# Sildr_1_0b.net
KiCad netlist of a schematic drawn in EAGLE
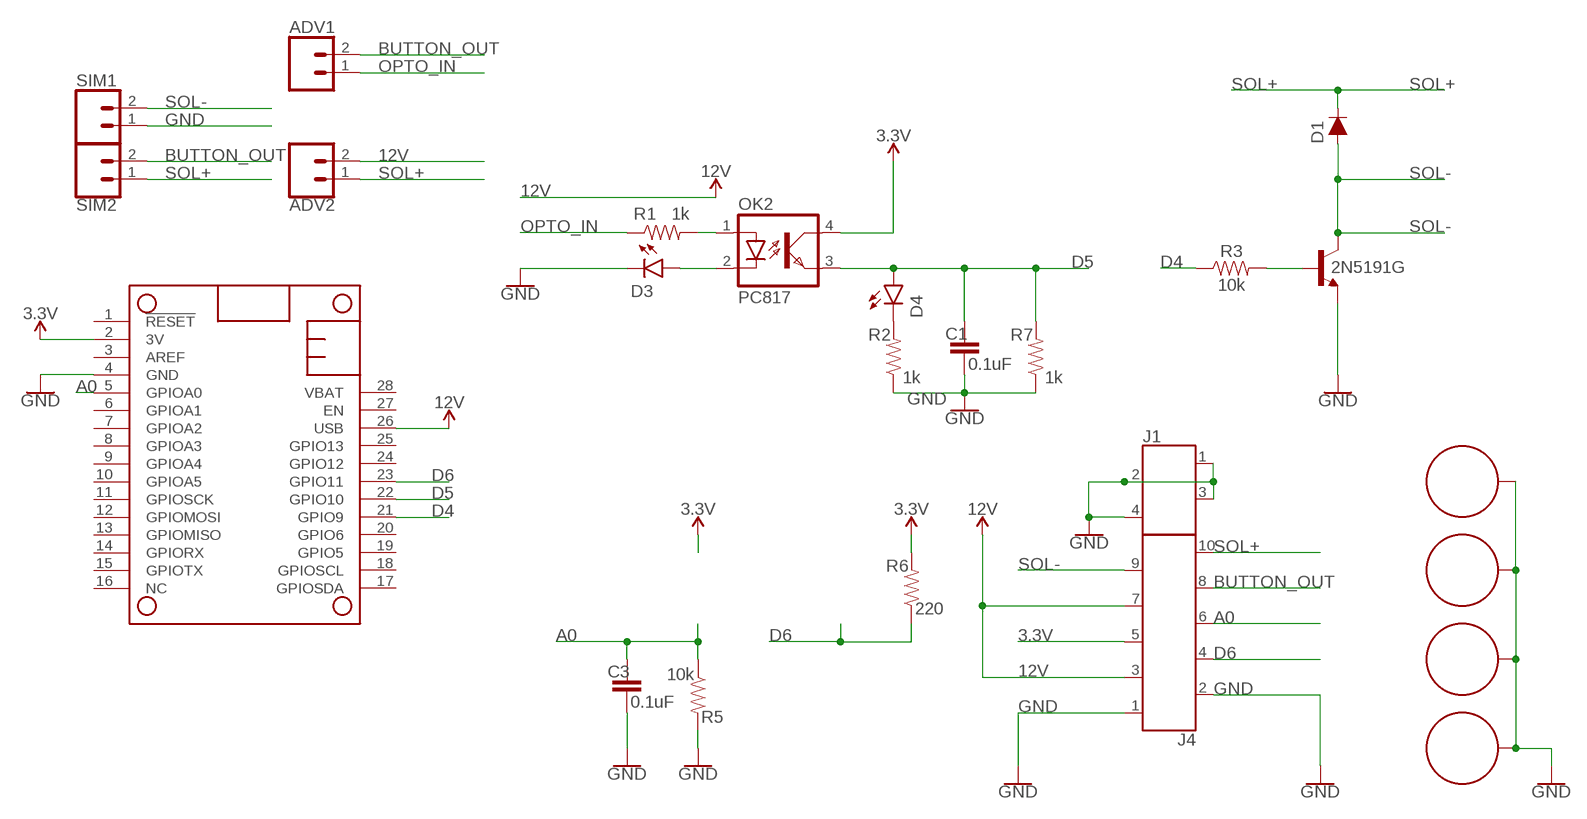
[diagram p0: schematic, sheet 1]

(export (version "E")
  (design (tool "Eeschema 10.0.6"))
  (components
    (comp (ref "2N5191G")
      (value "2SC1944")
      (footprint "eagle-import:T-30_V")
      (libsource (lib "eagle-import") (part "2SC1944"))
    )
    (comp (ref "ADV1")
      (value "CONN_02")
      (footprint "eagle-import:1X02")
      (libsource (lib "eagle-import") (part "CONN_02"))
    )
    (comp (ref "ADV2")
      (value "CONN_02")
      (footprint "eagle-import:1X02")
      (libsource (lib "eagle-import") (part "CONN_02"))
    )
    (comp (ref "C1")
      (value "0.1uF")
      (footprint "eagle-import:CAP-PTH-SMALL-KIT")
      (libsource (lib "eagle-import") (part "0.1UF-KIT-EZ-50V-20%"))
    )
    (comp (ref "C3")
      (value "0.1uF")
      (footprint "eagle-import:CAP-PTH-SMALL-KIT")
      (libsource (lib "eagle-import") (part "0.1UF-KIT-EZ-50V-20%"))
    )
    (comp (ref "D1")
      (value "1A/50V/1.1V")
      (footprint "eagle-import:DIODE-1N4001")
      (libsource (lib "eagle-import") (part "DIODE-PTH"))
    )
    (comp (ref "D3")
      (value "LED3MM")
      (footprint "eagle-import:LED_3MM")
      (libsource (lib "eagle-import") (part "LED3MM"))
    )
    (comp (ref "D4")
      (value "LED3MM")
      (footprint "eagle-import:LED_3MM")
      (libsource (lib "eagle-import") (part "LED3MM"))
    )
    (comp (ref "H1")
      (value "STANDOFF_ELECTRICAL")
      (footprint "eagle-import:STANDOFF-ELECTRICAL")
      (libsource (lib "eagle-import") (part "STANDOFF_ELECTRICAL"))
    )
    (comp (ref "H2")
      (value "STANDOFF_ELECTRICAL")
      (footprint "eagle-import:STANDOFF-ELECTRICAL")
      (libsource (lib "eagle-import") (part "STANDOFF_ELECTRICAL"))
    )
    (comp (ref "H3")
      (value "STANDOFF_ELECTRICAL")
      (footprint "eagle-import:STANDOFF-ELECTRICAL")
      (libsource (lib "eagle-import") (part "STANDOFF_ELECTRICAL"))
    )
    (comp (ref "H6")
      (value "STANDOFF_ELECTRICAL")
      (footprint "eagle-import:STANDOFF-ELECTRICAL")
      (libsource (lib "eagle-import") (part "STANDOFF_ELECTRICAL"))
    )
    (comp (ref "J1")
      (value "691412320004")
      (footprint "eagle-import:691412320004")
      (libsource (lib "eagle-import") (part "691412320004"))
    )
    (comp (ref "J4")
      (value "691412320010")
      (footprint "eagle-import:691412320010")
      (libsource (lib "eagle-import") (part "691412320010"))
    )
    (comp (ref "MS1")
      (value "FEATHERWING_NODIM")
      (footprint "eagle-import:FEATHERWING_DIM")
      (libsource (lib "eagle-import") (part "FEATHERWING_NODIM"))
    )
    (comp (ref "OK2")
      (value "PC817")
      (footprint "eagle-import:DIL04")
      (fields (field (name "MPN") "PC817X4J000F"))
      (libsource (lib "eagle-import") (part "PC817"))
    )
    (comp (ref "R1")
      (value "1k")
      (footprint "eagle-import:AXIAL-0.3")
      (libsource (lib "eagle-import") (part "10KOHM-HORIZ-1/4W-5%"))
    )
    (comp (ref "R2")
      (value "1k")
      (footprint "eagle-import:AXIAL-0.3")
      (libsource (lib "eagle-import") (part "10KOHM-HORIZ-1/4W-5%"))
    )
    (comp (ref "R3")
      (value "10k")
      (footprint "eagle-import:AXIAL-0.3")
      (libsource (lib "eagle-import") (part "10KOHM-HORIZ-1/4W-5%"))
    )
    (comp (ref "R5")
      (value "10k")
      (footprint "eagle-import:AXIAL-0.3")
      (libsource (lib "eagle-import") (part "10KOHM-HORIZ-1/4W-5%"))
    )
    (comp (ref "R6")
      (value "220")
      (footprint "eagle-import:AXIAL-0.3")
      (libsource (lib "eagle-import") (part "10KOHM-HORIZ-1/4W-5%"))
    )
    (comp (ref "R7")
      (value "1k")
      (footprint "eagle-import:AXIAL-0.3")
      (libsource (lib "eagle-import") (part "10KOHM-HORIZ-1/4W-5%"))
    )
    (comp (ref "SIM1")
      (value "CONN_02")
      (footprint "eagle-import:1X02")
      (libsource (lib "eagle-import") (part "CONN_02"))
    )
    (comp (ref "SIM2")
      (value "CONN_02")
      (footprint "eagle-import:1X02")
      (libsource (lib "eagle-import") (part "CONN_02"))
    )
  )
  (nets
    (net (code "1") (name "/A0") (class "Default")
      (node (ref "C3") (pin "1") (pinfunction "1_1") (pintype "passive"))
      (node (ref "J4") (pin "6") (pinfunction "6_6") (pintype "passive"))
      (node (ref "MS1") (pin "5") (pinfunction "GPIOA0_5") (pintype "bidirectional"))
      (node (ref "R5") (pin "P$1") (pinfunction "1_P$1") (pintype "passive"))
    )
    (net (code "2") (name "/BUTTON_OUT") (class "Default")
      (node (ref "ADV1") (pin "2") (pinfunction "2_2") (pintype "passive"))
      (node (ref "J4") (pin "8") (pinfunction "8_8") (pintype "passive"))
      (node (ref "SIM2") (pin "2") (pinfunction "2_2") (pintype "passive"))
    )
    (net (code "3") (name "/D4") (class "Default")
      (node (ref "MS1") (pin "21") (pinfunction "GPIO9_21") (pintype "bidirectional"))
      (node (ref "R3") (pin "P$1") (pinfunction "1_P$1") (pintype "passive"))
    )
    (net (code "4") (name "/D5") (class "Default")
      (node (ref "C1") (pin "1") (pinfunction "1_1") (pintype "passive"))
      (node (ref "D4") (pin "A") (pinfunction "A_A") (pintype "passive"))
      (node (ref "MS1") (pin "22") (pinfunction "GPIO10_22") (pintype "bidirectional"))
      (node (ref "OK2") (pin "3") (pinfunction "EMIT_3") (pintype "passive"))
      (node (ref "R7") (pin "P$2") (pinfunction "2_P$2") (pintype "passive"))
    )
    (net (code "5") (name "/D6") (class "Default")
      (node (ref "J4") (pin "4") (pinfunction "4_4") (pintype "passive"))
      (node (ref "MS1") (pin "23") (pinfunction "GPIO11_23") (pintype "bidirectional"))
      (node (ref "R6") (pin "P$1") (pinfunction "1_P$1") (pintype "passive"))
    )
    (net (code "6") (name "/OPTO_IN") (class "Default")
      (node (ref "ADV1") (pin "1") (pinfunction "1_1") (pintype "passive"))
      (node (ref "R1") (pin "P$1") (pinfunction "1_P$1") (pintype "passive"))
    )
    (net (code "7") (name "/SOL+") (class "Default")
      (node (ref "ADV2") (pin "1") (pinfunction "1_1") (pintype "passive"))
      (node (ref "D1") (pin "C") (pinfunction "C_C") (pintype "passive"))
      (node (ref "J4") (pin "10") (pinfunction "10_10") (pintype "passive"))
      (node (ref "SIM2") (pin "1") (pinfunction "1_1") (pintype "passive"))
    )
    (net (code "8") (name "/SOL-") (class "Default")
      (node (ref "2N5191G") (pin "2") (pinfunction "C_2") (pintype "passive"))
      (node (ref "D1") (pin "A") (pinfunction "A_A") (pintype "passive"))
      (node (ref "J4") (pin "9") (pinfunction "9_9") (pintype "passive"))
      (node (ref "SIM1") (pin "2") (pinfunction "2_2") (pintype "passive"))
    )
    (net (code "9") (name "/VBAT") (class "Default")
      (node (ref "MS1") (pin "28") (pinfunction "VBAT_28") (pintype "power_in"))
    )
    (net (code "10") (name "3.3V") (class "Default")
      (node (ref "J4") (pin "5") (pinfunction "5_5") (pintype "passive"))
      (node (ref "MS1") (pin "2") (pinfunction "3V_2") (pintype "power_in"))
      (node (ref "OK2") (pin "4") (pinfunction "COL_4") (pintype "passive"))
      (node (ref "R6") (pin "P$2") (pinfunction "2_P$2") (pintype "passive"))
    )
    (net (code "11") (name "12V") (class "Default")
      (node (ref "ADV2") (pin "2") (pinfunction "2_2") (pintype "passive"))
      (node (ref "J4") (pin "3") (pinfunction "3_3") (pintype "passive"))
      (node (ref "J4") (pin "7") (pinfunction "7_7") (pintype "passive"))
      (node (ref "MS1") (pin "26") (pinfunction "USB_26") (pintype "power_in"))
    )
    (net (code "12") (name "GND") (class "Default")
      (node (ref "2N5191G") (pin "3") (pinfunction "E_3") (pintype "passive"))
      (node (ref "C1") (pin "2") (pinfunction "2_2") (pintype "passive"))
      (node (ref "C3") (pin "2") (pinfunction "2_2") (pintype "passive"))
      (node (ref "D3") (pin "K") (pinfunction "C_K") (pintype "passive"))
      (node (ref "H1") (pin "P1") (pinfunction "P$1_P1") (pintype "bidirectional"))
      (node (ref "H2") (pin "P1") (pinfunction "P$1_P1") (pintype "bidirectional"))
      (node (ref "H3") (pin "P1") (pinfunction "P$1_P1") (pintype "bidirectional"))
      (node (ref "H6") (pin "P1") (pinfunction "P$1_P1") (pintype "bidirectional"))
      (node (ref "J1") (pin "1") (pinfunction "1_1") (pintype "passive"))
      (node (ref "J1") (pin "2") (pinfunction "2_2") (pintype "passive"))
      (node (ref "J1") (pin "3") (pinfunction "3_3") (pintype "passive"))
      (node (ref "J1") (pin "4") (pinfunction "4_4") (pintype "passive"))
      (node (ref "J4") (pin "1") (pinfunction "1_1") (pintype "passive"))
      (node (ref "J4") (pin "2") (pinfunction "2_2") (pintype "passive"))
      (node (ref "MS1") (pin "4") (pinfunction "GND_4") (pintype "power_in"))
      (node (ref "R2") (pin "P$1") (pinfunction "1_P$1") (pintype "passive"))
      (node (ref "R5") (pin "P$2") (pinfunction "2_P$2") (pintype "passive"))
      (node (ref "R7") (pin "P$1") (pinfunction "1_P$1") (pintype "passive"))
      (node (ref "SIM1") (pin "1") (pinfunction "1_1") (pintype "passive"))
    )
    (net (code "13") (name "Net-(2N5191G-B)") (class "Default")
      (node (ref "2N5191G") (pin "1") (pinfunction "B_1") (pintype "passive"))
      (node (ref "R3") (pin "P$2") (pinfunction "2_P$2") (pintype "passive"))
    )
    (net (code "14") (name "Net-(D4-C)") (class "Default")
      (node (ref "D4") (pin "K") (pinfunction "C_K") (pintype "passive"))
      (node (ref "R2") (pin "P$2") (pinfunction "2_P$2") (pintype "passive"))
    )
    (net (code "15") (name "Net-(OK2-A)") (class "Default")
      (node (ref "OK2") (pin "1") (pinfunction "A_1") (pintype "passive"))
      (node (ref "R1") (pin "P$2") (pinfunction "2_P$2") (pintype "passive"))
    )
    (net (code "16") (name "Net-(OK2-C)") (class "Default")
      (node (ref "D3") (pin "A") (pinfunction "A_A") (pintype "passive"))
      (node (ref "OK2") (pin "2") (pinfunction "C_2") (pintype "passive"))
    )
    (net (code "17") (name "unconnected-(MS1-AREF-Pad3)") (class "Default")
      (node (ref "MS1") (pin "3") (pinfunction "AREF_3") (pintype "passive"))
    )
    (net (code "18") (name "unconnected-(MS1-EN-Pad27)") (class "Default")
      (node (ref "MS1") (pin "27") (pinfunction "EN_27") (pintype "passive"))
    )
    (net (code "19") (name "unconnected-(MS1-GPIO5-Pad19)") (class "Default")
      (node (ref "MS1") (pin "19") (pinfunction "GPIO5_19") (pintype "bidirectional"))
    )
    (net (code "20") (name "unconnected-(MS1-GPIO6-Pad20)") (class "Default")
      (node (ref "MS1") (pin "20") (pinfunction "GPIO6_20") (pintype "bidirectional"))
    )
    (net (code "21") (name "unconnected-(MS1-GPIO12-Pad24)") (class "Default")
      (node (ref "MS1") (pin "24") (pinfunction "GPIO12_24") (pintype "bidirectional"))
    )
    (net (code "22") (name "unconnected-(MS1-GPIO13-Pad25)") (class "Default")
      (node (ref "MS1") (pin "25") (pinfunction "GPIO13_25") (pintype "bidirectional"))
    )
    (net (code "23") (name "unconnected-(MS1-GPIOA1-Pad6)") (class "Default")
      (node (ref "MS1") (pin "6") (pinfunction "GPIOA1_6") (pintype "bidirectional"))
    )
    (net (code "24") (name "unconnected-(MS1-GPIOA2-Pad7)") (class "Default")
      (node (ref "MS1") (pin "7") (pinfunction "GPIOA2_7") (pintype "bidirectional"))
    )
    (net (code "25") (name "unconnected-(MS1-GPIOA3-Pad8)") (class "Default")
      (node (ref "MS1") (pin "8") (pinfunction "GPIOA3_8") (pintype "bidirectional"))
    )
    (net (code "26") (name "unconnected-(MS1-GPIOA4-Pad9)") (class "Default")
      (node (ref "MS1") (pin "9") (pinfunction "GPIOA4_9") (pintype "bidirectional"))
    )
    (net (code "27") (name "unconnected-(MS1-GPIOA5-Pad10)") (class "Default")
      (node (ref "MS1") (pin "10") (pinfunction "GPIOA5_10") (pintype "bidirectional"))
    )
    (net (code "28") (name "unconnected-(MS1-GPIOMISO-Pad13)") (class "Default")
      (node (ref "MS1") (pin "13") (pinfunction "GPIOMISO_13") (pintype "bidirectional"))
    )
    (net (code "29") (name "unconnected-(MS1-GPIOMOSI-Pad12)") (class "Default")
      (node (ref "MS1") (pin "12") (pinfunction "GPIOMOSI_12") (pintype "bidirectional"))
    )
    (net (code "30") (name "unconnected-(MS1-GPIORX-Pad14)") (class "Default")
      (node (ref "MS1") (pin "14") (pinfunction "GPIORX_14") (pintype "bidirectional"))
    )
    (net (code "31") (name "unconnected-(MS1-GPIOSCK-Pad11)") (class "Default")
      (node (ref "MS1") (pin "11") (pinfunction "GPIOSCK_11") (pintype "bidirectional"))
    )
    (net (code "32") (name "unconnected-(MS1-GPIOSCL-Pad18)") (class "Default")
      (node (ref "MS1") (pin "18") (pinfunction "GPIOSCL_18") (pintype "bidirectional"))
    )
    (net (code "33") (name "unconnected-(MS1-GPIOSDA-Pad17)") (class "Default")
      (node (ref "MS1") (pin "17") (pinfunction "GPIOSDA_17") (pintype "bidirectional"))
    )
    (net (code "34") (name "unconnected-(MS1-GPIOTX-Pad15)") (class "Default")
      (node (ref "MS1") (pin "15") (pinfunction "GPIOTX_15") (pintype "bidirectional"))
    )
    (net (code "35") (name "unconnected-(MS1-NC-Pad16)") (class "Default")
      (node (ref "MS1") (pin "16") (pinfunction "NC_16") (pintype "passive"))
    )
    (net (code "36") (name "unconnected-(MS1-~{RESET}-Pad1)") (class "Default")
      (node (ref "MS1") (pin "1") (pinfunction "~{RESET}_1") (pintype "input"))
    )
  )
)
